# L293D.net
KiCad netlist of a schematic drawn in EAGLE
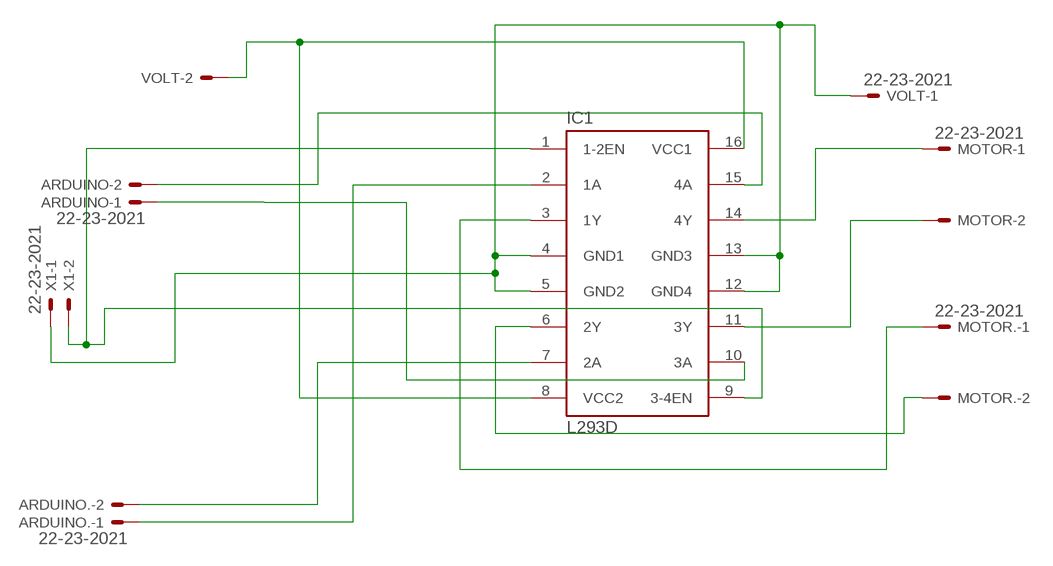
[diagram p0: schematic, sheet 1]

(export (version "E")
  (design (tool "Eeschema 10.0.6"))
  (components
    (comp (ref "ARDUINO")
      (value "22-23-2021")
      (footprint "eagle-import:22-23-2021")
      (fields (field (name "MF") "MOLEX"))
      (libsource (lib "eagle-import") (part "22-23-2021"))
    )
    (comp (ref "ARDUINO.")
      (value "22-23-2021")
      (footprint "eagle-import:22-23-2021")
      (fields (field (name "MF") "MOLEX"))
      (libsource (lib "eagle-import") (part "22-23-2021"))
    )
    (comp (ref "IC1")
      (value "L293D")
      (footprint "eagle-import:DIL16")
      (libsource (lib "eagle-import") (part "L293D"))
    )
    (comp (ref "MOTOR")
      (value "22-23-2021")
      (footprint "eagle-import:22-23-2021")
      (fields (field (name "MF") "MOLEX"))
      (libsource (lib "eagle-import") (part "22-23-2021"))
    )
    (comp (ref "MOTOR.")
      (value "22-23-2021")
      (footprint "eagle-import:22-23-2021")
      (fields (field (name "MF") "MOLEX"))
      (libsource (lib "eagle-import") (part "22-23-2021"))
    )
    (comp (ref "VOLT")
      (value "22-23-2021")
      (footprint "eagle-import:22-23-2021")
      (fields (field (name "MF") "MOLEX"))
      (libsource (lib "eagle-import") (part "22-23-2021"))
    )
    (comp (ref "X1")
      (value "22-23-2021")
      (footprint "eagle-import:22-23-2021")
      (fields (field (name "MF") "MOLEX"))
      (libsource (lib "eagle-import") (part "22-23-2021"))
    )
  )
  (nets
    (net (code "1") (name "Net-(ARDUINO.A-S)") (class "Default")
      (node (ref "ARDUINO.") (pin "1") (pinfunction "S_1") (pintype "passive"))
      (node (ref "IC1") (pin "2") (pinfunction "1A_2") (pintype "input"))
    )
    (net (code "2") (name "Net-(ARDUINO.B-S)") (class "Default")
      (node (ref "ARDUINO.") (pin "2") (pinfunction "S_2") (pintype "passive"))
      (node (ref "IC1") (pin "7") (pinfunction "2A_7") (pintype "input"))
    )
    (net (code "3") (name "Net-(ARDUINOA-S)") (class "Default")
      (node (ref "ARDUINO") (pin "1") (pinfunction "S_1") (pintype "passive"))
      (node (ref "IC1") (pin "10") (pinfunction "3A_10") (pintype "input"))
    )
    (net (code "4") (name "Net-(ARDUINOB-S)") (class "Default")
      (node (ref "ARDUINO") (pin "2") (pinfunction "S_2") (pintype "passive"))
      (node (ref "IC1") (pin "15") (pinfunction "4A_15") (pintype "input"))
    )
    (net (code "5") (name "Net-(IC1-1-2EN)") (class "Default")
      (node (ref "IC1") (pin "1") (pinfunction "1-2EN_1") (pintype "input"))
      (node (ref "IC1") (pin "9") (pinfunction "3-4EN_9") (pintype "input"))
      (node (ref "X1") (pin "2") (pinfunction "S_2") (pintype "passive"))
    )
    (net (code "6") (name "Net-(IC1-1Y)") (class "Default")
      (node (ref "IC1") (pin "3") (pinfunction "1Y_3") (pintype "output"))
      (node (ref "MOTOR.") (pin "1") (pinfunction "S_1") (pintype "passive"))
    )
    (net (code "7") (name "Net-(IC1-2Y)") (class "Default")
      (node (ref "IC1") (pin "6") (pinfunction "2Y_6") (pintype "output"))
      (node (ref "MOTOR.") (pin "2") (pinfunction "S_2") (pintype "passive"))
    )
    (net (code "8") (name "Net-(IC1-3Y)") (class "Default")
      (node (ref "IC1") (pin "11") (pinfunction "3Y_11") (pintype "output"))
      (node (ref "MOTOR") (pin "2") (pinfunction "S_2") (pintype "passive"))
    )
    (net (code "9") (name "Net-(IC1-4Y)") (class "Default")
      (node (ref "IC1") (pin "14") (pinfunction "4Y_14") (pintype "output"))
      (node (ref "MOTOR") (pin "1") (pinfunction "S_1") (pintype "passive"))
    )
    (net (code "10") (name "Net-(IC1-GND1)") (class "Default")
      (node (ref "IC1") (pin "12") (pinfunction "GND4_12") (pintype "power_in"))
      (node (ref "IC1") (pin "13") (pinfunction "GND3_13") (pintype "power_in"))
      (node (ref "IC1") (pin "4") (pinfunction "GND1_4") (pintype "power_in"))
      (node (ref "IC1") (pin "5") (pinfunction "GND2_5") (pintype "power_in"))
      (node (ref "VOLT") (pin "1") (pinfunction "S_1") (pintype "passive"))
      (node (ref "X1") (pin "1") (pinfunction "S_1") (pintype "passive"))
    )
    (net (code "11") (name "Net-(IC1-VCC1)") (class "Default")
      (node (ref "IC1") (pin "16") (pinfunction "VCC1_16") (pintype "power_in"))
      (node (ref "IC1") (pin "8") (pinfunction "VCC2_8") (pintype "power_in"))
      (node (ref "VOLT") (pin "2") (pinfunction "S_2") (pintype "passive"))
    )
  )
)
